# POWER_BIAS.net
KiCad netlist of a schematic drawn in Altium Designer
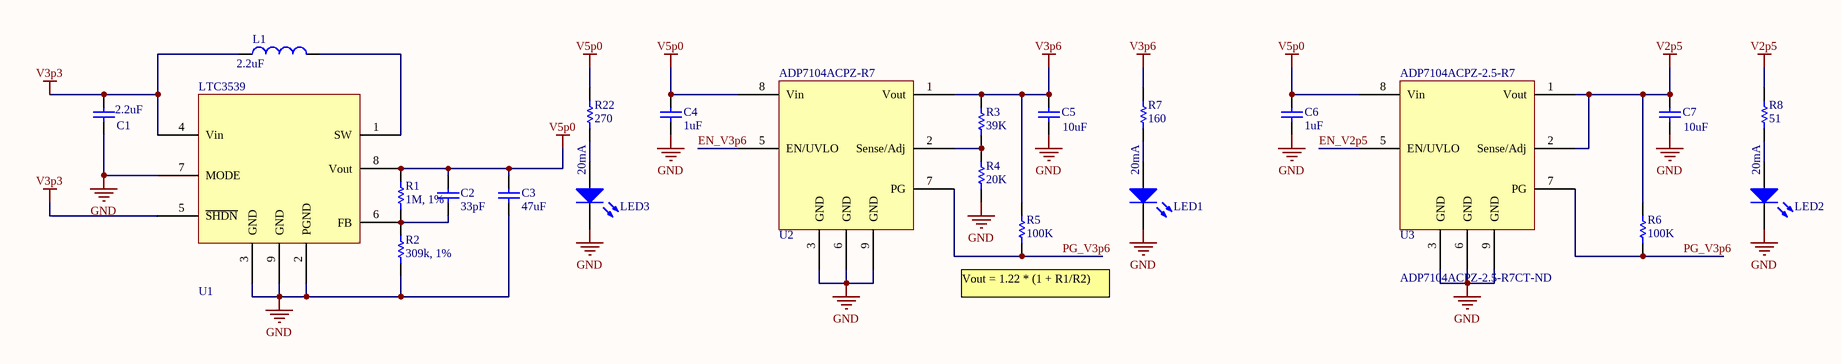
[diagram p0: POWER & BIAS.SchDoc]

(export (version "E")
  (design (tool "Eeschema 10.0.6"))
  (components
    (comp (ref "C1")
      (value "2.2uF")
      (footprint "CAPC1206(3216)170_N")
      (fields (field (name "Comment") "587-1329-2-ND"))
      (libsource (lib "Components") (part "CAP, 1206, 2.2uF"))
    )
    (comp (ref "C2")
      (value "33pF")
      (footprint "CAPC01005(0402)22_N")
      (fields (field (name "Comment") "CAP, 0402, 33pF"))
      (libsource (lib "Components") (part "CAP, 0402, 33pF"))
    )
    (comp (ref "C3")
      (value "47uF")
      (footprint "CAPC1206(3216)170_N")
      (fields (field (name "Comment") "CAP, 1206, 47uF"))
      (libsource (lib "Components") (part "CAP, 1206, 47uF"))
    )
    (comp (ref "C4")
      (value "1uF")
      (footprint "CAPC01005(0402)22_N")
      (fields (field (name "Comment") "CAP, 0402, 1uF"))
      (libsource (lib "Components") (part "CAP, 0402, 1uF"))
    )
    (comp (ref "C5")
      (value "10uF")
      (footprint "CAPC0805(2012)130_N")
      (fields (field (name "Comment") "CAP, 0805, 10uF"))
      (libsource (lib "Components") (part "CAP, 0805, 10uF"))
    )
    (comp (ref "C6")
      (value "1uF")
      (footprint "CAPC01005(0402)22_N")
      (fields (field (name "Comment") "CAP, 0402, 1uF"))
      (libsource (lib "Components") (part "CAP, 0402, 1uF"))
    )
    (comp (ref "C7")
      (value "10uF")
      (footprint "CAPC0805(2012)130_N")
      (fields (field (name "Comment") "CAP, 0805, 10uF"))
      (libsource (lib "Components") (part "CAP, 0805, 10uF"))
    )
    (comp (ref "L1")
      (value "2.2uF")
      (footprint "INDUCTOR, SMD, TDK")
      (fields (field (name "Comment") "INDUCTOR, SMD, 2.2uF"))
      (libsource (lib "Components") (part "INDUCTOR, SMD, 2.2uF"))
    )
    (comp (ref "LED1")
      (value "LED, GREEN, 0603, LITE-ON")
      (footprint "0603, LED")
      (libsource (lib "Components") (part "LED, GREEN, 0603, LITE-ON"))
    )
    (comp (ref "LED2")
      (value "LED, GREEN, 0603, LITE-ON")
      (footprint "0603, LED")
      (libsource (lib "Components") (part "LED, GREEN, 0603, LITE-ON"))
    )
    (comp (ref "LED3")
      (value "LED, GREEN, 0603, LITE-ON")
      (footprint "0603, LED")
      (libsource (lib "Components") (part "LED, GREEN, 0603, LITE-ON"))
    )
    (comp (ref "R1")
      (value "1M, 1%")
      (footprint "RESC0402(1005)_N")
      (fields (field (name "Comment") "RES, 0402, 1M, 1%"))
      (libsource (lib "Components") (part "RES, 0402, 1M, 1%"))
    )
    (comp (ref "R2")
      (value "309k, 1%")
      (footprint "RESC0402(1005)_N")
      (fields (field (name "Comment") "RES, 0402, 309k, 1%"))
      (libsource (lib "Components") (part "RES, 0402, 309k, 1%"))
    )
    (comp (ref "R3")
      (value "39K")
      (footprint "RES, 0603")
      (description "Resistor, 0603, 1/10W, 39K ohm")
      (fields
        (field (name "MANUFACTURER") "Panasonic Electronic Components")
        (field (name "MANUFACTURER PART NUMBER") "ERJ-3EKF3902V")
      )
      (libsource (lib "Resistors0603") (part "RES_0603_39K"))
    )
    (comp (ref "R4")
      (value "20K")
      (footprint "RES, 0603")
      (description "Resistor, 0603, 1/10W, 20K ohm")
      (fields
        (field (name "MANUFACTURER") "Panasonic Electronic Components")
        (field (name "MANUFACTURER PART NUMBER") "ERJ-3EKF2002V")
      )
      (libsource (lib "Resistors0603") (part "RES_0603_20K"))
    )
    (comp (ref "R5")
      (value "100K")
      (footprint "RES, 0603")
      (description "Resistor, 0603, 1/10W, 100K ohm")
      (fields
        (field (name "MANUFACTURER") "Panasonic Electronic Components")
        (field (name "MANUFACTURER PART NUMBER") "ERJ-3EKF1003V")
      )
      (libsource (lib "Resistors0603") (part "RES_0603_100K"))
    )
    (comp (ref "R6")
      (value "100K")
      (footprint "RES, 0603")
      (description "Resistor, 0603, 1/10W, 100K ohm")
      (fields
        (field (name "MANUFACTURER") "Panasonic Electronic Components")
        (field (name "MANUFACTURER PART NUMBER") "ERJ-3EKF1003V")
      )
      (libsource (lib "Resistors0603") (part "RES_0603_100K"))
    )
    (comp (ref "R7")
      (value "160")
      (footprint "RESC1005X04N")
      (description "Resistor, 0402, 1/10W, 160 ohm")
      (fields
        (field (name "MANUFACTURER") "Panasonic Electronic Components")
        (field (name "MANUFACTURER PART NUMBER") "ERJ-2RKF1600X")
      )
      (libsource (lib "Resistors0402") (part "RES_0402_160"))
    )
    (comp (ref "R8")
      (value "51")
      (footprint "RESC1005X04N")
      (description "Resistor, 0402, 1/10W, 51 ohm")
      (fields
        (field (name "MANUFACTURER") "Panasonic Electronic Components")
        (field (name "MANUFACTURER PART NUMBER") "ERJ-2RKF51R0X")
      )
      (libsource (lib "Resistors0402") (part "RES_0402_51"))
    )
    (comp (ref "R22")
      (value "270")
      (footprint "RES, 0603")
      (description "Resistor, 0603, 1/10W, 270 ohm")
      (fields
        (field (name "MANUFACTURER") "Panasonic Electronic Components")
        (field (name "MANUFACTURER PART NUMBER") "ERJ-3EKF2700V")
      )
      (libsource (lib "Resistors0603") (part "RES_0603_270"))
    )
    (comp (ref "U1")
      (value "LTC3539")
      (footprint "QFN45P300X200X80-8N")
      (description "2A, 1MHz/2MHz Synchronous Step-Up DC/DC Converters")
      (libsource (lib "Components") (part "LTC3539"))
    )
    (comp (ref "U2")
      (value "ADP7104ACPZ-R7")
      (footprint "QFN50P300X300X75-8N")
      (description "Adjustable Voltage Regulator")
      (libsource (lib "Components") (part "ADP7104ACPZ-R7"))
    )
    (comp (ref "U3")
      (value "ADP7104ACPZ-2.5-R7")
      (footprint "QFN50P300X300X75-8N")
      (description "2.5V Voltage Regulator")
      (fields (field (name "SUPPLIER PART NUMBER 1") "ADP7104ACPZ-2.5-R7CT-ND"))
      (libsource (lib "Components") (part "ADP7104ACPZ-2.5-R7"))
    )
  )
  (nets
    (net (code "1") (name "/EN_V2p5") (class "Default")
      (node (ref "U3") (pin "5") (pinfunction "EN/UVLO_5") (pintype "passive"))
    )
    (net (code "2") (name "/EN_V3p6") (class "Default")
      (node (ref "U2") (pin "5") (pinfunction "EN/UVLO_5") (pintype "passive"))
    )
    (net (code "3") (name "/PG_V3p6") (class "Default")
      (node (ref "R5") (pin "1") (pinfunction "1_1") (pintype "passive"))
      (node (ref "R6") (pin "1") (pinfunction "1_1") (pintype "passive"))
      (node (ref "U2") (pin "7") (pinfunction "PG_7") (pintype "passive"))
      (node (ref "U3") (pin "7") (pinfunction "PG_7") (pintype "passive"))
    )
    (net (code "4") (name "GND") (class "Default")
      (node (ref "C1") (pin "1") (pinfunction "1_1") (pintype "passive"))
      (node (ref "C3") (pin "1") (pinfunction "1_1") (pintype "passive"))
      (node (ref "C4") (pin "1") (pinfunction "1_1") (pintype "passive"))
      (node (ref "C5") (pin "1") (pinfunction "1_1") (pintype "passive"))
      (node (ref "C6") (pin "1") (pinfunction "1_1") (pintype "passive"))
      (node (ref "C7") (pin "1") (pinfunction "1_1") (pintype "passive"))
      (node (ref "LED1") (pin "1") (pinfunction "C_1") (pintype "passive"))
      (node (ref "LED2") (pin "1") (pinfunction "C_1") (pintype "passive"))
      (node (ref "LED3") (pin "1") (pinfunction "C_1") (pintype "passive"))
      (node (ref "R2") (pin "1") (pinfunction "1_1") (pintype "passive"))
      (node (ref "R4") (pin "1") (pinfunction "1_1") (pintype "passive"))
      (node (ref "U1") (pin "2") (pinfunction "PGND_2") (pintype "passive"))
      (node (ref "U1") (pin "3") (pinfunction "GND_3") (pintype "passive"))
      (node (ref "U1") (pin "7") (pinfunction "MODE_7") (pintype "passive"))
      (node (ref "U1") (pin "9") (pinfunction "GND_9") (pintype "passive"))
      (node (ref "U2") (pin "3") (pinfunction "GND_3") (pintype "passive"))
      (node (ref "U2") (pin "6") (pinfunction "GND_6") (pintype "passive"))
      (node (ref "U2") (pin "9") (pinfunction "GND_9") (pintype "passive"))
      (node (ref "U3") (pin "3") (pinfunction "GND_3") (pintype "passive"))
      (node (ref "U3") (pin "6") (pinfunction "GND_6") (pintype "passive"))
      (node (ref "U3") (pin "9") (pinfunction "GND_9") (pintype "passive"))
    )
    (net (code "5") (name "Net-(LED1-A)") (class "Default")
      (node (ref "LED1") (pin "2") (pinfunction "A_2") (pintype "passive"))
      (node (ref "R7") (pin "1") (pinfunction "1_1") (pintype "passive"))
    )
    (net (code "6") (name "Net-(LED2-A)") (class "Default")
      (node (ref "LED2") (pin "2") (pinfunction "A_2") (pintype "passive"))
      (node (ref "R8") (pin "1") (pinfunction "1_1") (pintype "passive"))
    )
    (net (code "7") (name "Net-(LED3-A)") (class "Default")
      (node (ref "LED3") (pin "2") (pinfunction "A_2") (pintype "passive"))
      (node (ref "R22") (pin "1") (pinfunction "1_1") (pintype "passive"))
    )
    (net (code "8") (name "Net-(U1-FB)") (class "Default")
      (node (ref "C2") (pin "1") (pinfunction "1_1") (pintype "passive"))
      (node (ref "R1") (pin "1") (pinfunction "1_1") (pintype "passive"))
      (node (ref "R2") (pin "2") (pinfunction "2_2") (pintype "passive"))
      (node (ref "U1") (pin "6") (pinfunction "FB_6") (pintype "passive"))
    )
    (net (code "9") (name "Net-(U1-SW)") (class "Default")
      (node (ref "L1") (pin "2") (pinfunction "2_2") (pintype "passive"))
      (node (ref "U1") (pin "1") (pinfunction "SW_1") (pintype "passive"))
    )
    (net (code "10") (name "Net-(U2-Sense{slash}Adj)") (class "Default")
      (node (ref "R3") (pin "1") (pinfunction "1_1") (pintype "passive"))
      (node (ref "R4") (pin "2") (pinfunction "2_2") (pintype "passive"))
      (node (ref "U2") (pin "2") (pinfunction "Sense/Adj_2") (pintype "passive"))
    )
    (net (code "11") (name "V2p5") (class "Default")
      (node (ref "C7") (pin "2") (pinfunction "2_2") (pintype "passive"))
      (node (ref "R6") (pin "2") (pinfunction "2_2") (pintype "passive"))
      (node (ref "R8") (pin "2") (pinfunction "2_2") (pintype "passive"))
      (node (ref "U3") (pin "1") (pinfunction "Vout_1") (pintype "passive"))
      (node (ref "U3") (pin "2") (pinfunction "Sense/Adj_2") (pintype "passive"))
    )
    (net (code "12") (name "V3p3") (class "Default")
      (node (ref "C1") (pin "2") (pinfunction "2_2") (pintype "passive"))
      (node (ref "L1") (pin "1") (pinfunction "1_1") (pintype "passive"))
      (node (ref "U1") (pin "4") (pinfunction "Vin_4") (pintype "passive"))
      (node (ref "U1") (pin "5") (pinfunction "~{SHDN}_5") (pintype "passive"))
    )
    (net (code "13") (name "V3p6") (class "Default")
      (node (ref "C5") (pin "2") (pinfunction "2_2") (pintype "passive"))
      (node (ref "R3") (pin "2") (pinfunction "2_2") (pintype "passive"))
      (node (ref "R5") (pin "2") (pinfunction "2_2") (pintype "passive"))
      (node (ref "R7") (pin "2") (pinfunction "2_2") (pintype "passive"))
      (node (ref "U2") (pin "1") (pinfunction "Vout_1") (pintype "passive"))
    )
    (net (code "14") (name "V5p0") (class "Default")
      (node (ref "C2") (pin "2") (pinfunction "2_2") (pintype "passive"))
      (node (ref "C3") (pin "2") (pinfunction "2_2") (pintype "passive"))
      (node (ref "C4") (pin "2") (pinfunction "2_2") (pintype "passive"))
      (node (ref "C6") (pin "2") (pinfunction "2_2") (pintype "passive"))
      (node (ref "R1") (pin "2") (pinfunction "2_2") (pintype "passive"))
      (node (ref "R22") (pin "2") (pinfunction "2_2") (pintype "passive"))
      (node (ref "U1") (pin "8") (pinfunction "Vout_8") (pintype "passive"))
      (node (ref "U2") (pin "8") (pinfunction "Vin_8") (pintype "passive"))
      (node (ref "U3") (pin "8") (pinfunction "Vin_8") (pintype "passive"))
    )
  )
)
